# lps25h_board.net
KiCad netlist of a schematic drawn in EAGLE
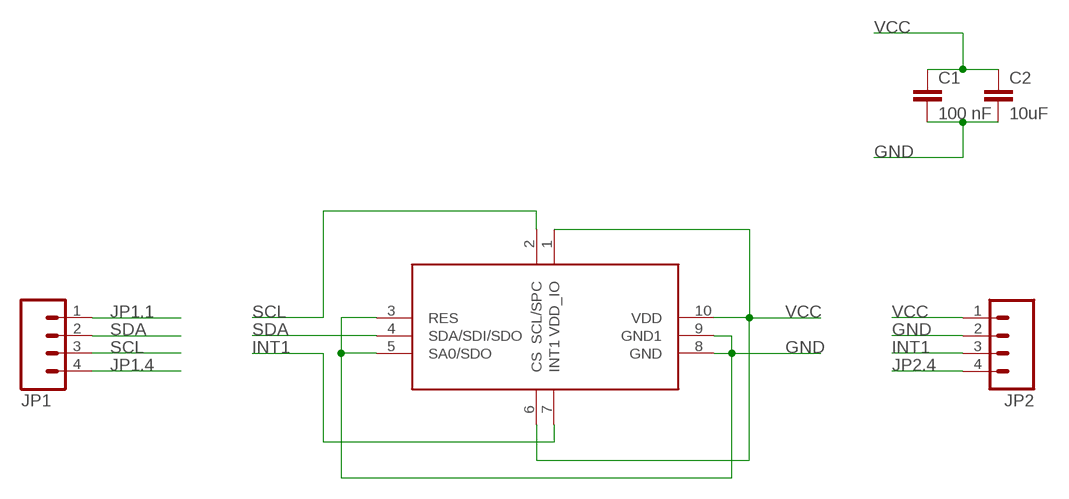
[diagram p0: schematic, sheet 1]

(export (version "E")
  (design (tool "Eeschema 10.0.6"))
  (components
    (comp (ref "C1")
      (value "100 nF")
      (footprint "eagle-import:0805")
      (libsource (lib "eagle-import") (part "CAP0805"))
    )
    (comp (ref "C2")
      (value "10uF")
      (footprint "eagle-import:0805")
      (libsource (lib "eagle-import") (part "CAP0805"))
    )
    (comp (ref "JP1")
      (value "M04PTH")
      (footprint "eagle-import:1X04")
      (libsource (lib "eagle-import") (part "M04PTH"))
    )
    (comp (ref "JP2")
      (value "M04PTH")
      (footprint "eagle-import:1X04")
      (libsource (lib "eagle-import") (part "M04PTH"))
    )
    (comp (ref "U$1")
      (value "LPS25H")
      (footprint "eagle-import:LPS25H_PADS")
      (libsource (lib "eagle-import") (part "LPS25H"))
    )
  )
  (nets
    (net (code "1") (name "/GND") (class "Default")
      (node (ref "C1") (pin "2") (pinfunction "2_2") (pintype "passive"))
      (node (ref "C2") (pin "2") (pinfunction "2_2") (pintype "passive"))
      (node (ref "JP2") (pin "2") (pinfunction "2_2") (pintype "passive"))
      (node (ref "U$1") (pin "3") (pinfunction "RES_3") (pintype "bidirectional"))
      (node (ref "U$1") (pin "5") (pinfunction "SA0/SDO_5") (pintype "bidirectional"))
      (node (ref "U$1") (pin "8") (pinfunction "GND_8") (pintype "bidirectional"))
      (node (ref "U$1") (pin "9") (pinfunction "GND1_9") (pintype "bidirectional"))
    )
    (net (code "2") (name "/INT1") (class "Default")
      (node (ref "JP2") (pin "3") (pinfunction "3_3") (pintype "passive"))
      (node (ref "U$1") (pin "7") (pinfunction "INT1_7") (pintype "bidirectional"))
    )
    (net (code "3") (name "/JP1.1") (class "Default")
      (node (ref "JP1") (pin "1") (pinfunction "1_1") (pintype "passive"))
    )
    (net (code "4") (name "/JP1.4") (class "Default")
      (node (ref "JP1") (pin "4") (pinfunction "4_4") (pintype "passive"))
    )
    (net (code "5") (name "/JP2.4") (class "Default")
      (node (ref "JP2") (pin "4") (pinfunction "4_4") (pintype "passive"))
    )
    (net (code "6") (name "/SCL") (class "Default")
      (node (ref "JP1") (pin "3") (pinfunction "3_3") (pintype "passive"))
      (node (ref "U$1") (pin "2") (pinfunction "SCL/SPC_2") (pintype "bidirectional"))
    )
    (net (code "7") (name "/SDA") (class "Default")
      (node (ref "JP1") (pin "2") (pinfunction "2_2") (pintype "passive"))
      (node (ref "U$1") (pin "4") (pinfunction "SDA/SDI/SDO_4") (pintype "bidirectional"))
    )
    (net (code "8") (name "/VCC") (class "Default")
      (node (ref "C1") (pin "1") (pinfunction "1_1") (pintype "passive"))
      (node (ref "C2") (pin "1") (pinfunction "1_1") (pintype "passive"))
      (node (ref "JP2") (pin "1") (pinfunction "1_1") (pintype "passive"))
      (node (ref "U$1") (pin "1") (pinfunction "VDD_IO_1") (pintype "bidirectional"))
      (node (ref "U$1") (pin "10") (pinfunction "VDD_10") (pintype "bidirectional"))
      (node (ref "U$1") (pin "6") (pinfunction "CS_6") (pintype "bidirectional"))
    )
  )
)
